# mcuBoard.net
KiCad netlist of a schematic drawn in EAGLE
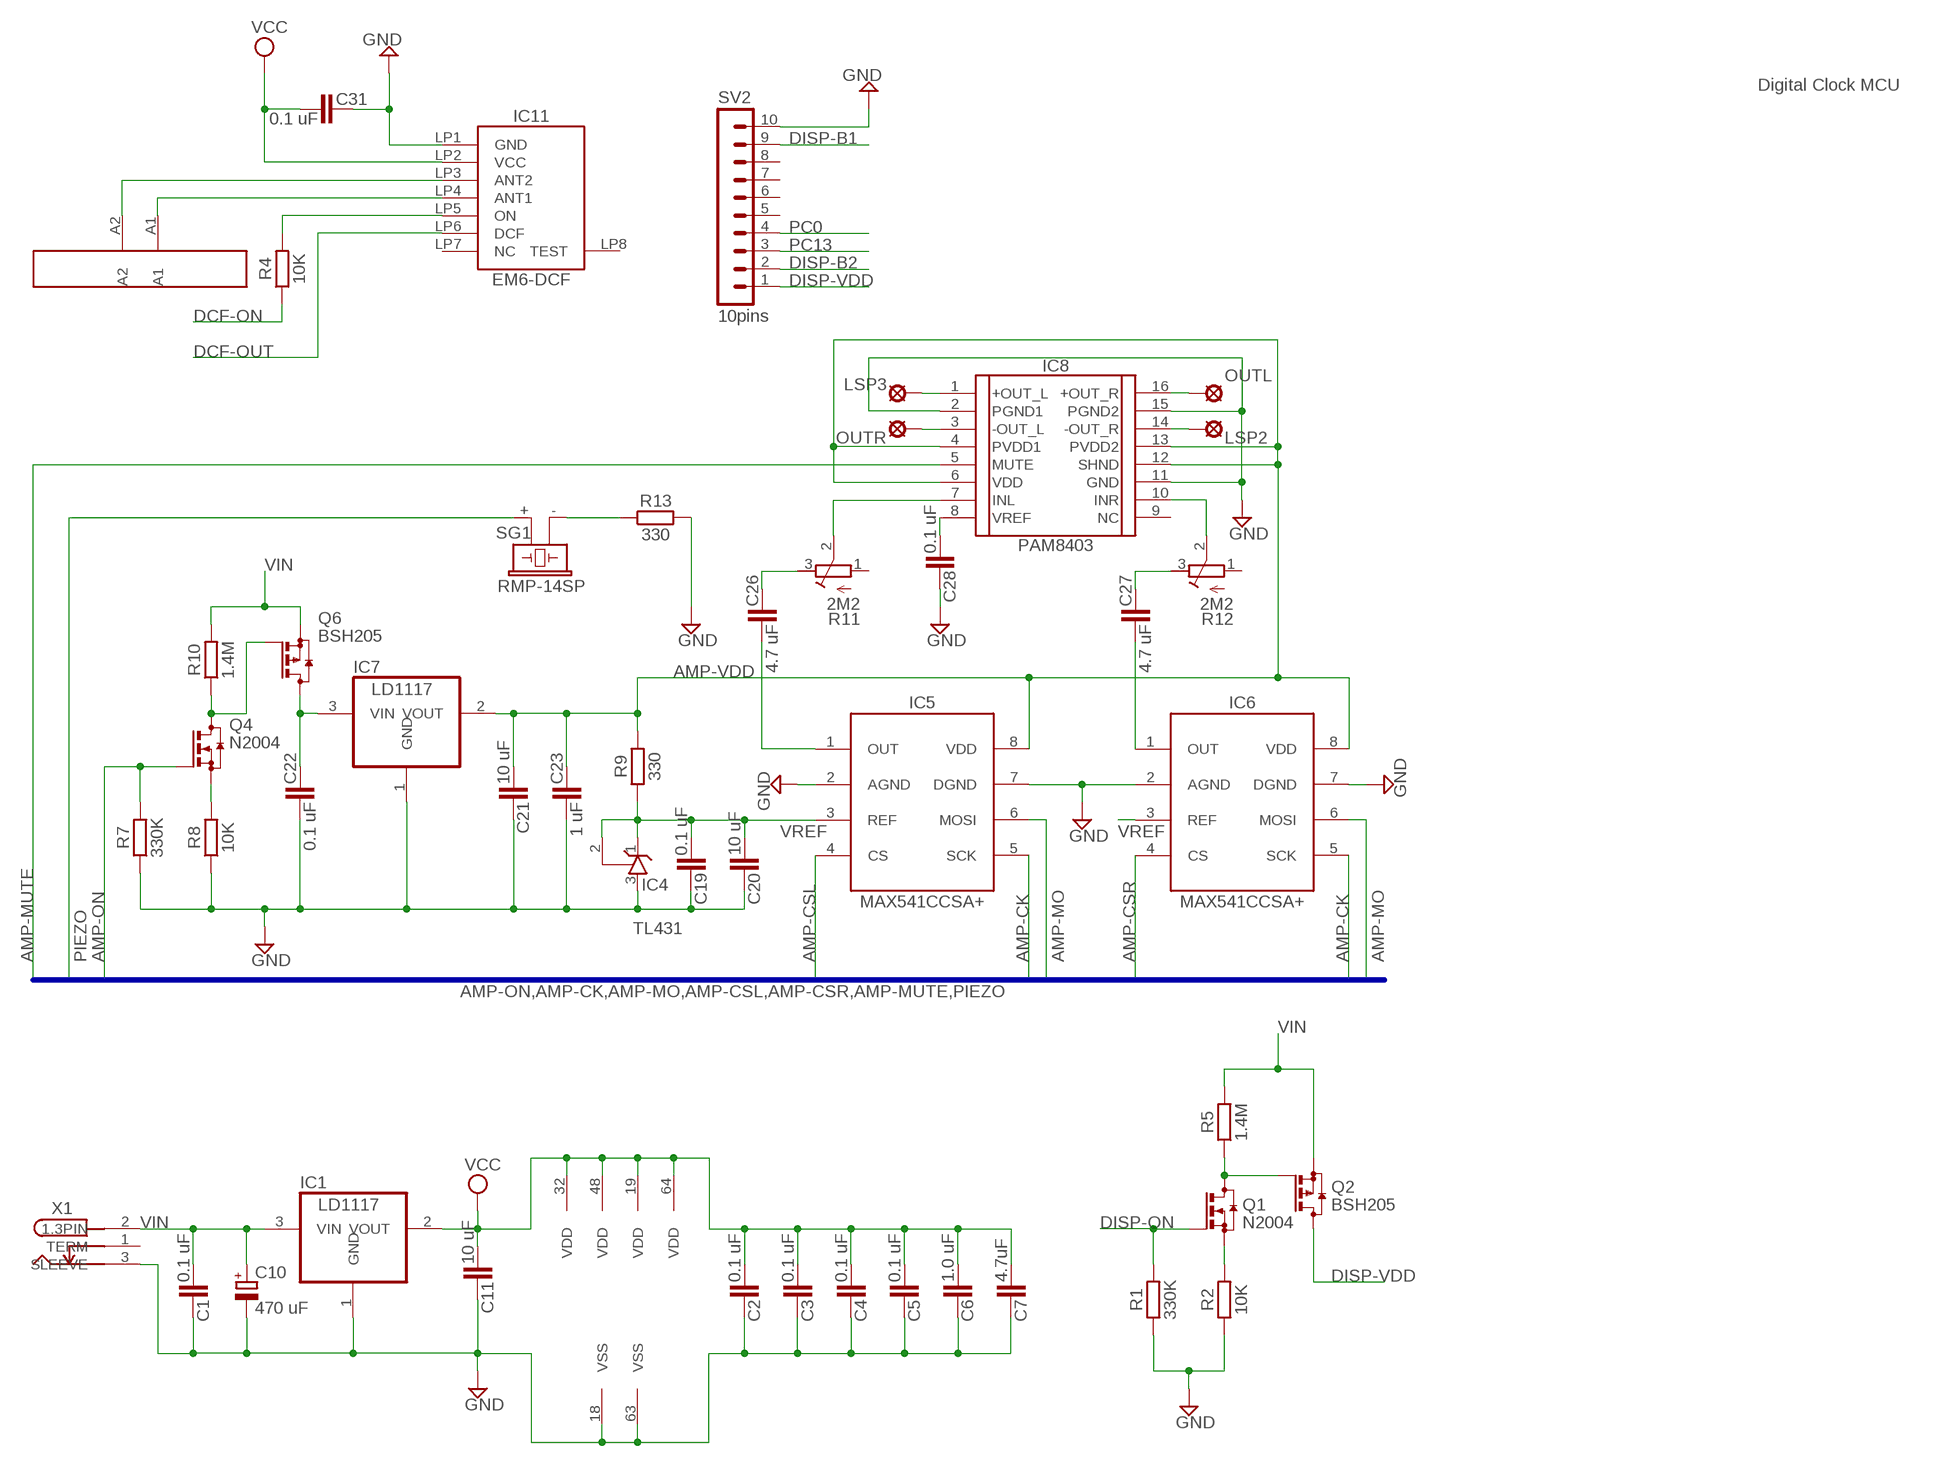
[diagram p0: schematic, sheet 1, part 1 of 2]
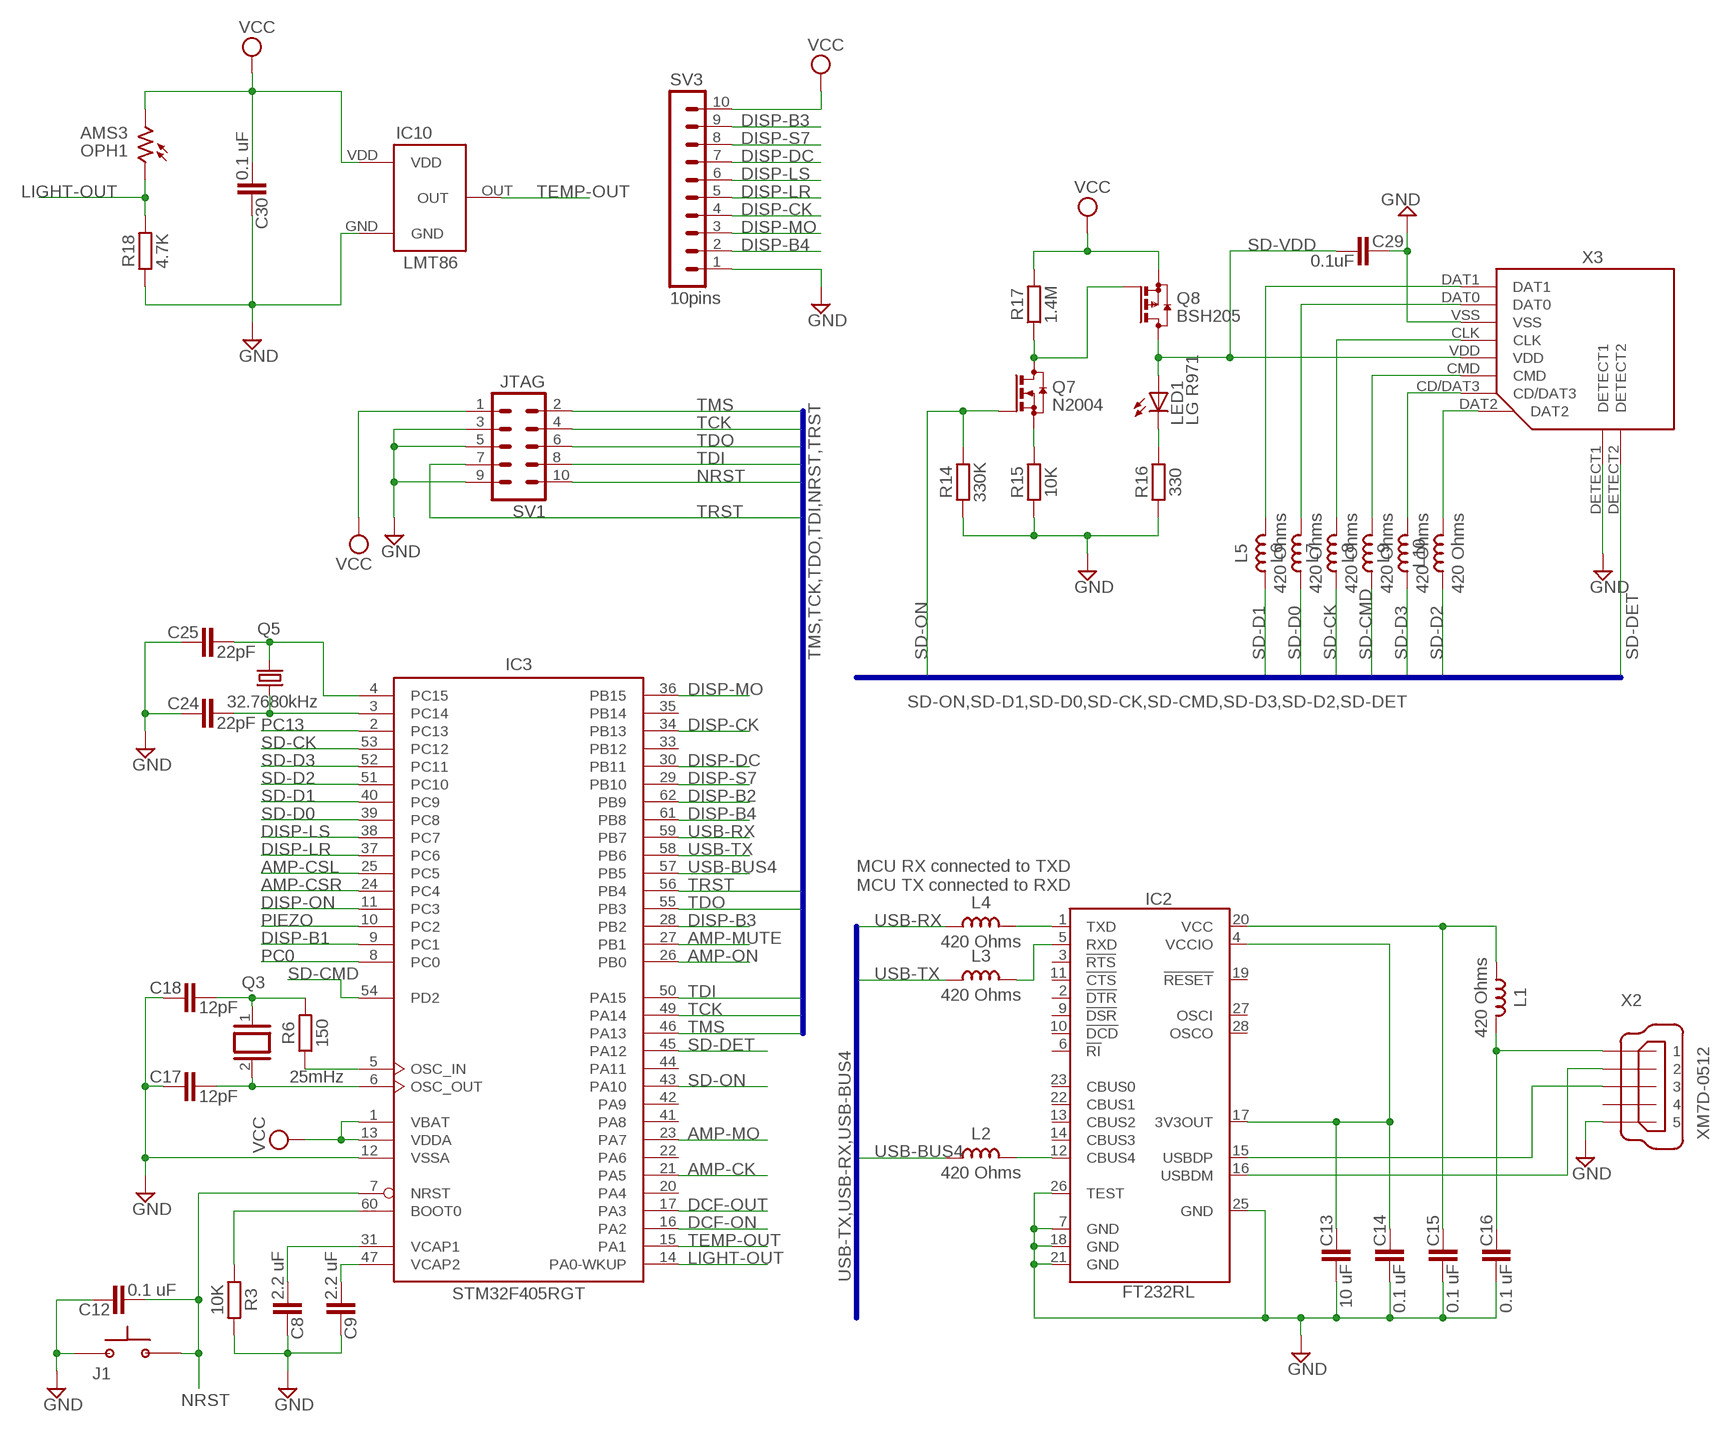
[diagram p1: schematic, sheet 1, part 2 of 2]

(export (version "E")
  (design (tool "Eeschema 10.0.6"))
  (components
    (comp (ref "A1")
      (value "DCF77-ANT")
      (footprint "eagle-import:DCF77-ANT")
      (libsource (lib "eagle-import") (part "DCF77-ANT"))
    )
    (comp (ref "C1")
      (value "0.1 uF")
      (footprint "eagle-import:C1206")
      (libsource (lib "eagle-import") (part "C-EUC1206"))
    )
    (comp (ref "C2")
      (value "0.1 uF")
      (footprint "eagle-import:C1206")
      (libsource (lib "eagle-import") (part "C-EUC1206"))
    )
    (comp (ref "C3")
      (value "0.1 uF")
      (footprint "eagle-import:C1206")
      (libsource (lib "eagle-import") (part "C-EUC1206"))
    )
    (comp (ref "C4")
      (value "0.1 uF")
      (footprint "eagle-import:C1206")
      (libsource (lib "eagle-import") (part "C-EUC1206"))
    )
    (comp (ref "C5")
      (value "0.1 uF")
      (footprint "eagle-import:C1206")
      (libsource (lib "eagle-import") (part "C-EUC1206"))
    )
    (comp (ref "C6")
      (value "1.0 uF")
      (footprint "eagle-import:C1206")
      (libsource (lib "eagle-import") (part "C-EUC1206"))
    )
    (comp (ref "C7")
      (value "4.7uF")
      (footprint "eagle-import:C1206")
      (libsource (lib "eagle-import") (part "C-EUC1206"))
    )
    (comp (ref "C8")
      (value "2.2 uF")
      (footprint "eagle-import:C1206")
      (libsource (lib "eagle-import") (part "C-EUC1206"))
    )
    (comp (ref "C9")
      (value "2.2 uF")
      (footprint "eagle-import:C1206")
      (libsource (lib "eagle-import") (part "C-EUC1206"))
    )
    (comp (ref "C10")
      (value "470 uF")
      (footprint "eagle-import:TT5D11L")
      (libsource (lib "eagle-import") (part "CPOL-EUTT5D11L"))
    )
    (comp (ref "C11")
      (value "10 uF")
      (footprint "eagle-import:C1206")
      (libsource (lib "eagle-import") (part "C-EUC1206"))
    )
    (comp (ref "C12")
      (value "0.1 uF")
      (footprint "eagle-import:C1206")
      (libsource (lib "eagle-import") (part "C-EUC1206"))
    )
    (comp (ref "C13")
      (value "10 uF")
      (footprint "eagle-import:C1206")
      (libsource (lib "eagle-import") (part "C-EUC1206"))
    )
    (comp (ref "C14")
      (value "0.1 uF")
      (footprint "eagle-import:C1206")
      (libsource (lib "eagle-import") (part "C-EUC1206"))
    )
    (comp (ref "C15")
      (value "0.1 uF")
      (footprint "eagle-import:C1206")
      (libsource (lib "eagle-import") (part "C-EUC1206"))
    )
    (comp (ref "C16")
      (value "0.1 uF")
      (footprint "eagle-import:C1206")
      (libsource (lib "eagle-import") (part "C-EUC1206"))
    )
    (comp (ref "C17")
      (value "12pF")
      (footprint "eagle-import:C1206")
      (libsource (lib "eagle-import") (part "C-EUC1206"))
    )
    (comp (ref "C18")
      (value "12pF")
      (footprint "eagle-import:C1206")
      (libsource (lib "eagle-import") (part "C-EUC1206"))
    )
    (comp (ref "C19")
      (value "0.1 uF")
      (footprint "eagle-import:C1206")
      (libsource (lib "eagle-import") (part "C-EUC1206"))
    )
    (comp (ref "C20")
      (value "10 uF")
      (footprint "eagle-import:C1206")
      (libsource (lib "eagle-import") (part "C-EUC1206"))
    )
    (comp (ref "C21")
      (value "10 uF")
      (footprint "eagle-import:C1206")
      (libsource (lib "eagle-import") (part "C-EUC1206"))
    )
    (comp (ref "C22")
      (value "0.1 uF")
      (footprint "eagle-import:C1206")
      (libsource (lib "eagle-import") (part "C-EUC1206"))
    )
    (comp (ref "C23")
      (value "1 uF")
      (footprint "eagle-import:C1206")
      (libsource (lib "eagle-import") (part "C-EUC1206"))
    )
    (comp (ref "C24")
      (value "22pF")
      (footprint "eagle-import:C1206")
      (libsource (lib "eagle-import") (part "C-EUC1206"))
    )
    (comp (ref "C25")
      (value "22pF")
      (footprint "eagle-import:C1206")
      (libsource (lib "eagle-import") (part "C-EUC1206"))
    )
    (comp (ref "C26")
      (value "4.7 uF")
      (footprint "eagle-import:C1206")
      (libsource (lib "eagle-import") (part "C-EUC1206"))
    )
    (comp (ref "C27")
      (value "4.7 uF")
      (footprint "eagle-import:C1206")
      (libsource (lib "eagle-import") (part "C-EUC1206"))
    )
    (comp (ref "C28")
      (value "0.1 uF")
      (footprint "eagle-import:C1206")
      (libsource (lib "eagle-import") (part "C-EUC1206"))
    )
    (comp (ref "C29")
      (value "0.1uF")
      (footprint "eagle-import:C1206")
      (libsource (lib "eagle-import") (part "C-EUC1206"))
    )
    (comp (ref "C30")
      (value "0.1 uF")
      (footprint "eagle-import:C1206")
      (libsource (lib "eagle-import") (part "C-EUC1206"))
    )
    (comp (ref "C31")
      (value "0.1 uF")
      (footprint "eagle-import:C1206")
      (libsource (lib "eagle-import") (part "C-EUC1206"))
    )
    (comp (ref "IC1")
      (value "LD1117")
      (footprint "eagle-import:SOT223")
      (fields (field (name "MPN") "REG1117"))
      (libsource (lib "eagle-import") (part "REG1117"))
    )
    (comp (ref "IC2")
      (value "FT232RL")
      (footprint "eagle-import:SSOP28")
      (libsource (lib "eagle-import") (part "FT232RL"))
    )
    (comp (ref "IC3")
      (value "STM32F405RGT")
      (footprint "eagle-import:LQFP64")
      (libsource (lib "eagle-import") (part "STM32F405RTG"))
    )
    (comp (ref "IC4")
      (value "TL431")
      (footprint "eagle-import:SOT-23")
      (libsource (lib "eagle-import") (part "TL431CL3T"))
    )
    (comp (ref "IC5")
      (value "MAX541CCSA+")
      (footprint "eagle-import:SOIC-8")
      (libsource (lib "eagle-import") (part "MAX541"))
    )
    (comp (ref "IC6")
      (value "MAX541CCSA+")
      (footprint "eagle-import:SOIC-8")
      (libsource (lib "eagle-import") (part "MAX541"))
    )
    (comp (ref "IC7")
      (value "LD1117")
      (footprint "eagle-import:SOT223")
      (fields (field (name "MPN") "REG1117"))
      (libsource (lib "eagle-import") (part "REG1117"))
    )
    (comp (ref "IC8")
      (value "PAM8403")
      (footprint "eagle-import:SOP-16")
      (libsource (lib "eagle-import") (part "PAM8403"))
    )
    (comp (ref "IC10")
      (value "LMT86")
      (footprint "eagle-import:LMT86")
      (libsource (lib "eagle-import") (part "LMT86"))
    )
    (comp (ref "IC11")
      (value "DCF77")
      (footprint "eagle-import:DCF77")
      (libsource (lib "eagle-import") (part "DCF77"))
    )
    (comp (ref "J1")
      (value "BUTTON-FSM14JRT")
      (footprint "eagle-import:BUTTON-FSM14JRT")
      (libsource (lib "eagle-import") (part "BUTTON-FSM14JRT"))
    )
    (comp (ref "L1")
      (value "420 Ohms")
      (footprint "eagle-import:L0603")
      (libsource (lib "eagle-import") (part "L0603"))
    )
    (comp (ref "L2")
      (value "420 Ohms")
      (footprint "eagle-import:L0603")
      (libsource (lib "eagle-import") (part "L0603"))
    )
    (comp (ref "L3")
      (value "420 Ohms")
      (footprint "eagle-import:L0603")
      (libsource (lib "eagle-import") (part "L0603"))
    )
    (comp (ref "L4")
      (value "420 Ohms")
      (footprint "eagle-import:L0603")
      (libsource (lib "eagle-import") (part "L0603"))
    )
    (comp (ref "L5")
      (value "420 Ohms")
      (footprint "eagle-import:L0603")
      (libsource (lib "eagle-import") (part "L0603"))
    )
    (comp (ref "L6")
      (value "420 Ohms")
      (footprint "eagle-import:L0603")
      (libsource (lib "eagle-import") (part "L0603"))
    )
    (comp (ref "L7")
      (value "420 Ohms")
      (footprint "eagle-import:L0603")
      (libsource (lib "eagle-import") (part "L0603"))
    )
    (comp (ref "L8")
      (value "420 Ohms")
      (footprint "eagle-import:L0603")
      (libsource (lib "eagle-import") (part "L0603"))
    )
    (comp (ref "L9")
      (value "420 Ohms")
      (footprint "eagle-import:L0603")
      (libsource (lib "eagle-import") (part "L0603"))
    )
    (comp (ref "L10")
      (value "420 Ohms")
      (footprint "eagle-import:L0603")
      (libsource (lib "eagle-import") (part "L0603"))
    )
    (comp (ref "LED1")
      (value "LG R971")
      (footprint "eagle-import:CHIP-LED0805")
      (libsource (lib "eagle-import") (part "LEDCHIP-LED0805"))
    )
    (comp (ref "LSP2")
      (value "LSP10")
      (footprint "eagle-import:LSP10")
      (libsource (lib "eagle-import") (part "LSP10"))
    )
    (comp (ref "LSP3")
      (value "LSP10")
      (footprint "eagle-import:LSP10")
      (libsource (lib "eagle-import") (part "LSP10"))
    )
    (comp (ref "OPH1")
      (value "AMS3")
      (footprint "eagle-import:VT900")
      (libsource (lib "eagle-import") (part "VT935GB"))
    )
    (comp (ref "OUTL")
      (value "LSP10")
      (footprint "eagle-import:LSP10")
      (libsource (lib "eagle-import") (part "LSP10"))
    )
    (comp (ref "OUTR")
      (value "LSP10")
      (footprint "eagle-import:LSP10")
      (libsource (lib "eagle-import") (part "LSP10"))
    )
    (comp (ref "Q1")
      (value "N2004")
      (footprint "eagle-import:SOT23")
      (libsource (lib "eagle-import") (part "BSS123"))
    )
    (comp (ref "Q2")
      (value "BSH205")
      (footprint "eagle-import:SOT23")
      (libsource (lib "eagle-import") (part "BSS84"))
    )
    (comp (ref "Q3")
      (value "25mHz")
      (footprint "eagle-import:HC-46X")
      (libsource (lib "eagle-import") (part "HC-46X"))
    )
    (comp (ref "Q4")
      (value "N2004")
      (footprint "eagle-import:SOT23")
      (libsource (lib "eagle-import") (part "BSS123"))
    )
    (comp (ref "Q5")
      (value "32.7680kHz")
      (footprint "eagle-import:MC-306")
      (fields (field (name "MPN") "MC-306 60.0KHZ  100PPM ,12.5PF"))
      (libsource (lib "eagle-import") (part "MC-306"))
    )
    (comp (ref "Q6")
      (value "BSH205")
      (footprint "eagle-import:SOT23")
      (libsource (lib "eagle-import") (part "BSS84"))
    )
    (comp (ref "Q7")
      (value "N2004")
      (footprint "eagle-import:SOT23")
      (libsource (lib "eagle-import") (part "BSS123"))
    )
    (comp (ref "Q8")
      (value "BSH205")
      (footprint "eagle-import:SOT23")
      (libsource (lib "eagle-import") (part "BSS84"))
    )
    (comp (ref "R1")
      (value "330K")
      (footprint "eagle-import:R1206")
      (libsource (lib "eagle-import") (part "R-EU_R1206"))
    )
    (comp (ref "R2")
      (value "10K")
      (footprint "eagle-import:R1206")
      (libsource (lib "eagle-import") (part "R-EU_R1206"))
    )
    (comp (ref "R3")
      (value "10K")
      (footprint "eagle-import:R1206")
      (libsource (lib "eagle-import") (part "R-EU_R1206"))
    )
    (comp (ref "R4")
      (value "10K")
      (footprint "eagle-import:R1206")
      (libsource (lib "eagle-import") (part "R-EU_R1206"))
    )
    (comp (ref "R5")
      (value "1.4M")
      (footprint "eagle-import:R1206")
      (libsource (lib "eagle-import") (part "R-EU_R1206"))
    )
    (comp (ref "R6")
      (value "150")
      (footprint "eagle-import:R1206")
      (libsource (lib "eagle-import") (part "R-EU_R1206"))
    )
    (comp (ref "R7")
      (value "330K")
      (footprint "eagle-import:R1206")
      (libsource (lib "eagle-import") (part "R-EU_R1206"))
    )
    (comp (ref "R8")
      (value "10K")
      (footprint "eagle-import:R1206")
      (libsource (lib "eagle-import") (part "R-EU_R1206"))
    )
    (comp (ref "R9")
      (value "330")
      (footprint "eagle-import:R1206")
      (libsource (lib "eagle-import") (part "R-EU_R1206"))
    )
    (comp (ref "R10")
      (value "1.4M")
      (footprint "eagle-import:R1206")
      (libsource (lib "eagle-import") (part "R-EU_R1206"))
    )
    (comp (ref "R11")
      (value "2M2")
      (footprint "eagle-import:R-TRIM-3362U")
      (libsource (lib "eagle-import") (part "R-TRIM3362U"))
    )
    (comp (ref "R12")
      (value "2M2")
      (footprint "eagle-import:R-TRIM-3362U")
      (libsource (lib "eagle-import") (part "R-TRIM3362U"))
    )
    (comp (ref "R13")
      (value "330")
      (footprint "eagle-import:R1206")
      (libsource (lib "eagle-import") (part "R-EU_R1206"))
    )
    (comp (ref "R14")
      (value "330K")
      (footprint "eagle-import:R1206")
      (libsource (lib "eagle-import") (part "R-EU_R1206"))
    )
    (comp (ref "R15")
      (value "10K")
      (footprint "eagle-import:R1206")
      (libsource (lib "eagle-import") (part "R-EU_R1206"))
    )
    (comp (ref "R16")
      (value "330")
      (footprint "eagle-import:R1206")
      (libsource (lib "eagle-import") (part "R-EU_R1206"))
    )
    (comp (ref "R17")
      (value "1.4M")
      (footprint "eagle-import:R1206")
      (libsource (lib "eagle-import") (part "R-EU_R1206"))
    )
    (comp (ref "R18")
      (value "4.7K")
      (footprint "eagle-import:R1206")
      (libsource (lib "eagle-import") (part "R-EU_R1206"))
    )
    (comp (ref "SG1")
      (value "RMP-14SP")
      (footprint "eagle-import:F_CM12P")
      (libsource (lib "eagle-import") (part "F/CM12P"))
    )
    (comp (ref "SV1")
      (value "JTAG")
      (footprint "eagle-import:MA05-2")
      (libsource (lib "eagle-import") (part "MA05-2"))
    )
    (comp (ref "SV2")
      (value "10pins")
      (footprint "eagle-import:MA10-1")
      (libsource (lib "eagle-import") (part "MA10-1"))
    )
    (comp (ref "SV3")
      (value "10pins")
      (footprint "eagle-import:MA10-1")
      (libsource (lib "eagle-import") (part "MA10-1"))
    )
    (comp (ref "X1")
      (value "DC-8N")
      (footprint "eagle-import:BUCHSE-1.3X3.75")
      (libsource (lib "eagle-import") (part "DC-8N"))
    )
    (comp (ref "X2")
      (value "XM7D-0512")
      (footprint "eagle-import:XM7D-0512")
      (libsource (lib "eagle-import") (part "MINI-USB-5-DPI32005-601"))
    )
    (comp (ref "X3")
      (value "MICRO-SD-DM3AT")
      (footprint "eagle-import:DM3AT")
      (libsource (lib "eagle-import") (part "MICRO-SD-DM3AT"))
    )
  )
  (nets
    (net (code "1") (name "/AMP-CK") (class "Default")
      (node (ref "IC3") (pin "21") (pinfunction "PA5_21") (pintype "bidirectional"))
      (node (ref "IC5") (pin "5") (pinfunction "SCK_5") (pintype "bidirectional"))
      (node (ref "IC6") (pin "5") (pinfunction "SCK_5") (pintype "bidirectional"))
    )
    (net (code "2") (name "/AMP-CSL") (class "Default")
      (node (ref "IC3") (pin "25") (pinfunction "PC5_25") (pintype "bidirectional"))
      (node (ref "IC5") (pin "4") (pinfunction "CS_4") (pintype "bidirectional"))
    )
    (net (code "3") (name "/AMP-CSR") (class "Default")
      (node (ref "IC3") (pin "24") (pinfunction "PC4_24") (pintype "bidirectional"))
      (node (ref "IC6") (pin "4") (pinfunction "CS_4") (pintype "bidirectional"))
    )
    (net (code "4") (name "/AMP-MO") (class "Default")
      (node (ref "IC3") (pin "23") (pinfunction "PA7_23") (pintype "bidirectional"))
      (node (ref "IC5") (pin "6") (pinfunction "MOSI_6") (pintype "bidirectional"))
      (node (ref "IC6") (pin "6") (pinfunction "MOSI_6") (pintype "bidirectional"))
    )
    (net (code "5") (name "/AMP-MUTE") (class "Default")
      (node (ref "IC3") (pin "27") (pinfunction "PB1_27") (pintype "bidirectional"))
      (node (ref "IC8") (pin "5") (pinfunction "MUTE_5") (pintype "bidirectional"))
    )
    (net (code "6") (name "/AMP-ON") (class "Default")
      (node (ref "IC3") (pin "26") (pinfunction "PB0_26") (pintype "bidirectional"))
      (node (ref "Q4") (pin "1") (pinfunction "G_1") (pintype "passive"))
      (node (ref "R7") (pin "2") (pinfunction "2_2") (pintype "passive"))
    )
    (net (code "7") (name "/AMP-VDD") (class "Default")
      (node (ref "C21") (pin "2") (pinfunction "2_2") (pintype "passive"))
      (node (ref "C23") (pin "1") (pinfunction "1_1") (pintype "passive"))
      (node (ref "IC5") (pin "8") (pinfunction "VDD_8") (pintype "bidirectional"))
      (node (ref "IC6") (pin "8") (pinfunction "VDD_8") (pintype "bidirectional"))
      (node (ref "IC7") (pin "2") (pinfunction "VOUT_2") (pintype "power_in"))
      (node (ref "IC8") (pin "12") (pinfunction "SHND_12") (pintype "bidirectional"))
      (node (ref "IC8") (pin "13") (pinfunction "PVDD2_13") (pintype "bidirectional"))
      (node (ref "IC8") (pin "4") (pinfunction "PVDD1_4") (pintype "bidirectional"))
      (node (ref "IC8") (pin "6") (pinfunction "VDD_6") (pintype "bidirectional"))
      (node (ref "R9") (pin "2") (pinfunction "2_2") (pintype "passive"))
    )
    (net (code "8") (name "/DCF-ON") (class "Default")
      (node (ref "IC3") (pin "16") (pinfunction "PA2_16") (pintype "bidirectional"))
      (node (ref "R4") (pin "1") (pinfunction "1_1") (pintype "passive"))
    )
    (net (code "9") (name "/DCF-OUT") (class "Default")
      (node (ref "IC11") (pin "LP6") (pinfunction "DCF_LP6") (pintype "bidirectional"))
      (node (ref "IC3") (pin "17") (pinfunction "PA3_17") (pintype "bidirectional"))
    )
    (net (code "10") (name "/DISP-B1") (class "Default")
      (node (ref "IC3") (pin "9") (pinfunction "PC1_9") (pintype "bidirectional"))
      (node (ref "SV2") (pin "9") (pinfunction "9_9") (pintype "passive"))
    )
    (net (code "11") (name "/DISP-B2") (class "Default")
      (node (ref "IC3") (pin "62") (pinfunction "PB9_62") (pintype "bidirectional"))
      (node (ref "SV2") (pin "2") (pinfunction "2_2") (pintype "passive"))
    )
    (net (code "12") (name "/DISP-B3") (class "Default")
      (node (ref "IC3") (pin "28") (pinfunction "PB2_28") (pintype "bidirectional"))
      (node (ref "SV3") (pin "9") (pinfunction "9_9") (pintype "passive"))
    )
    (net (code "13") (name "/DISP-B4") (class "Default")
      (node (ref "IC3") (pin "61") (pinfunction "PB8_61") (pintype "bidirectional"))
      (node (ref "SV3") (pin "2") (pinfunction "2_2") (pintype "passive"))
    )
    (net (code "14") (name "/DISP-CK") (class "Default")
      (node (ref "IC3") (pin "34") (pinfunction "PB13_34") (pintype "bidirectional"))
      (node (ref "SV3") (pin "4") (pinfunction "4_4") (pintype "passive"))
    )
    (net (code "15") (name "/DISP-DC") (class "Default")
      (node (ref "IC3") (pin "30") (pinfunction "PB11_30") (pintype "bidirectional"))
      (node (ref "SV3") (pin "7") (pinfunction "7_7") (pintype "passive"))
    )
    (net (code "16") (name "/DISP-LR") (class "Default")
      (node (ref "IC3") (pin "37") (pinfunction "PC6_37") (pintype "bidirectional"))
      (node (ref "SV3") (pin "5") (pinfunction "5_5") (pintype "passive"))
    )
    (net (code "17") (name "/DISP-LS") (class "Default")
      (node (ref "IC3") (pin "38") (pinfunction "PC7_38") (pintype "bidirectional"))
      (node (ref "SV3") (pin "6") (pinfunction "6_6") (pintype "passive"))
    )
    (net (code "18") (name "/DISP-MO") (class "Default")
      (node (ref "IC3") (pin "36") (pinfunction "PB15_36") (pintype "bidirectional"))
      (node (ref "SV3") (pin "3") (pinfunction "3_3") (pintype "passive"))
    )
    (net (code "19") (name "/DISP-ON") (class "Default")
      (node (ref "IC3") (pin "11") (pinfunction "PC3_11") (pintype "bidirectional"))
      (node (ref "Q1") (pin "1") (pinfunction "G_1") (pintype "passive"))
      (node (ref "R1") (pin "2") (pinfunction "2_2") (pintype "passive"))
    )
    (net (code "20") (name "/DISP-S7") (class "Default")
      (node (ref "IC3") (pin "29") (pinfunction "PB10_29") (pintype "bidirectional"))
      (node (ref "SV3") (pin "8") (pinfunction "8_8") (pintype "passive"))
    )
    (net (code "21") (name "/DISP-VDD") (class "Default")
      (node (ref "Q2") (pin "3") (pinfunction "D_3") (pintype "passive"))
      (node (ref "SV2") (pin "1") (pinfunction "1_1") (pintype "passive"))
    )
    (net (code "22") (name "/LIGHT-OUT") (class "Default")
      (node (ref "IC3") (pin "14") (pinfunction "PA0-WKUP_14") (pintype "bidirectional"))
      (node (ref "OPH1") (pin "1") (pinfunction "1_1") (pintype "passive"))
      (node (ref "R18") (pin "2") (pinfunction "2_2") (pintype "passive"))
    )
    (net (code "23") (name "/NRST") (class "Default")
      (node (ref "C12") (pin "2") (pinfunction "2_2") (pintype "passive"))
      (node (ref "IC3") (pin "7") (pinfunction "NRST_7") (pintype "bidirectional"))
      (node (ref "J1") (pin "P$2") (pinfunction "2_P$2") (pintype "bidirectional"))
      (node (ref "SV1") (pin "10") (pinfunction "10_10") (pintype "passive"))
    )
    (net (code "24") (name "/PC0") (class "Default")
      (node (ref "IC3") (pin "8") (pinfunction "PC0_8") (pintype "bidirectional"))
      (node (ref "SV2") (pin "4") (pinfunction "4_4") (pintype "passive"))
    )
    (net (code "25") (name "/PC13") (class "Default")
      (node (ref "IC3") (pin "2") (pinfunction "PC13_2") (pintype "bidirectional"))
      (node (ref "SV2") (pin "3") (pinfunction "3_3") (pintype "passive"))
    )
    (net (code "26") (name "/PIEZO") (class "Default")
      (node (ref "IC3") (pin "10") (pinfunction "PC2_10") (pintype "bidirectional"))
      (node (ref "SG1") (pin "+") (pinfunction "1_+") (pintype "passive"))
    )
    (net (code "27") (name "/SD-CK") (class "Default")
      (node (ref "IC3") (pin "53") (pinfunction "PC12_53") (pintype "bidirectional"))
      (node (ref "L7") (pin "1") (pinfunction "1_1") (pintype "passive"))
    )
    (net (code "28") (name "/SD-CMD") (class "Default")
      (node (ref "IC3") (pin "54") (pinfunction "PD2_54") (pintype "bidirectional"))
      (node (ref "L8") (pin "1") (pinfunction "1_1") (pintype "passive"))
    )
    (net (code "29") (name "/SD-D0") (class "Default")
      (node (ref "IC3") (pin "39") (pinfunction "PC8_39") (pintype "bidirectional"))
      (node (ref "L6") (pin "1") (pinfunction "1_1") (pintype "passive"))
    )
    (net (code "30") (name "/SD-D1") (class "Default")
      (node (ref "IC3") (pin "40") (pinfunction "PC9_40") (pintype "bidirectional"))
      (node (ref "L5") (pin "1") (pinfunction "1_1") (pintype "passive"))
    )
    (net (code "31") (name "/SD-D2") (class "Default")
      (node (ref "IC3") (pin "51") (pinfunction "PC10_51") (pintype "bidirectional"))
      (node (ref "L10") (pin "1") (pinfunction "1_1") (pintype "passive"))
    )
    (net (code "32") (name "/SD-D3") (class "Default")
      (node (ref "IC3") (pin "52") (pinfunction "PC11_52") (pintype "bidirectional"))
      (node (ref "L9") (pin "1") (pinfunction "1_1") (pintype "passive"))
    )
    (net (code "33") (name "/SD-DET") (class "Default")
      (node (ref "IC3") (pin "45") (pinfunction "PA12_45") (pintype "bidirectional"))
      (node (ref "X3") (pin "DETECT2") (pinfunction "DETECT2_DETECT2") (pintype "bidirectional"))
    )
    (net (code "34") (name "/SD-ON") (class "Default")
      (node (ref "IC3") (pin "43") (pinfunction "PA10_43") (pintype "bidirectional"))
      (node (ref "Q7") (pin "1") (pinfunction "G_1") (pintype "passive"))
      (node (ref "R14") (pin "2") (pinfunction "2_2") (pintype "passive"))
    )
    (net (code "35") (name "/SD-VDD") (class "Default")
      (node (ref "C29") (pin "2") (pinfunction "2_2") (pintype "passive"))
      (node (ref "LED1") (pin "A") (pinfunction "A_A") (pintype "passive"))
      (node (ref "Q8") (pin "3") (pinfunction "D_3") (pintype "passive"))
      (node (ref "X3") (pin "VDD") (pinfunction "VDD_VDD") (pintype "power_in"))
    )
    (net (code "36") (name "/TCK") (class "Default")
      (node (ref "IC3") (pin "49") (pinfunction "PA14_49") (pintype "bidirectional"))
      (node (ref "SV1") (pin "4") (pinfunction "4_4") (pintype "passive"))
    )
    (net (code "37") (name "/TDI") (class "Default")
      (node (ref "IC3") (pin "50") (pinfunction "PA15_50") (pintype "bidirectional"))
      (node (ref "SV1") (pin "8") (pinfunction "8_8") (pintype "passive"))
    )
    (net (code "38") (name "/TDO") (class "Default")
      (node (ref "IC3") (pin "55") (pinfunction "PB3_55") (pintype "bidirectional"))
      (node (ref "SV1") (pin "6") (pinfunction "6_6") (pintype "passive"))
    )
    (net (code "39") (name "/TEMP-OUT") (class "Default")
      (node (ref "IC10") (pin "OUT") (pinfunction "OUT_OUT") (pintype "bidirectional"))
      (node (ref "IC3") (pin "15") (pinfunction "PA1_15") (pintype "bidirectional"))
    )
    (net (code "40") (name "/TMS") (class "Default")
      (node (ref "IC3") (pin "46") (pinfunction "PA13_46") (pintype "bidirectional"))
      (node (ref "SV1") (pin "2") (pinfunction "2_2") (pintype "passive"))
    )
    (net (code "41") (name "/TRST") (class "Default")
      (node (ref "IC3") (pin "56") (pinfunction "PB4_56") (pintype "bidirectional"))
      (node (ref "SV1") (pin "7") (pinfunction "7_7") (pintype "passive"))
    )
    (net (code "42") (name "/USB-BUS4") (class "Default")
      (node (ref "IC3") (pin "57") (pinfunction "PB5_57") (pintype "bidirectional"))
      (node (ref "L2") (pin "2") (pinfunction "2_2") (pintype "passive"))
    )
    (net (code "43") (name "/USB-RX") (class "Default")
      (node (ref "IC3") (pin "59") (pinfunction "PB7_59") (pintype "bidirectional"))
      (node (ref "L4") (pin "1") (pinfunction "1_1") (pintype "passive"))
    )
    (net (code "44") (name "/USB-TX") (class "Default")
      (node (ref "IC3") (pin "58") (pinfunction "PB6_58") (pintype "bidirectional"))
      (node (ref "L3") (pin "1") (pinfunction "1_1") (pintype "passive"))
    )
    (net (code "45") (name "/VIN") (class "Default")
      (node (ref "C1") (pin "2") (pinfunction "2_2") (pintype "passive"))
      (node (ref "C10") (pin "+") (pinfunction "+_+") (pintype "passive"))
      (node (ref "IC1") (pin "3") (pinfunction "VIN_3") (pintype "input"))
      (node (ref "Q2") (pin "2") (pinfunction "S_2") (pintype "passive"))
      (node (ref "Q6") (pin "2") (pinfunction "S_2") (pintype "passive"))
      (node (ref "R10") (pin "2") (pinfunction "2_2") (pintype "passive"))
      (node (ref "R5") (pin "2") (pinfunction "2_2") (pintype "passive"))
      (node (ref "X1") (pin "2") (pinfunction "1.3PIN_2") (pintype "power_in"))
    )
    (net (code "46") (name "/VREF") (class "Default")
      (node (ref "C19") (pin "2") (pinfunction "2_2") (pintype "passive"))
      (node (ref "C20") (pin "2") (pinfunction "2_2") (pintype "passive"))
      (node (ref "IC4") (pin "1") (pinfunction "C_1") (pintype "passive"))
      (node (ref "IC4") (pin "2") (pinfunction "R_2") (pintype "passive"))
      (node (ref "IC5") (pin "3") (pinfunction "REF_3") (pintype "bidirectional"))
      (node (ref "IC6") (pin "3") (pinfunction "REF_3") (pintype "bidirectional"))
      (node (ref "R9") (pin "1") (pinfunction "1_1") (pintype "passive"))
    )
    (net (code "51") (name "GND") (class "Default")
      (node (ref "C1") (pin "1") (pinfunction "1_1") (pintype "passive"))
      (node (ref "C10") (pin "-") (pinfunction "-_-") (pintype "passive"))
      (node (ref "C11") (pin "1") (pinfunction "1_1") (pintype "passive"))
      (node (ref "C12") (pin "1") (pinfunction "1_1") (pintype "passive"))
      (node (ref "C13") (pin "2") (pinfunction "2_2") (pintype "passive"))
      (node (ref "C14") (pin "2") (pinfunction "2_2") (pintype "passive"))
      (node (ref "C15") (pin "2") (pinfunction "2_2") (pintype "passive"))
      (node (ref "C16") (pin "2") (pinfunction "2_2") (pintype "passive"))
      (node (ref "C17") (pin "1") (pinfunction "1_1") (pintype "passive"))
      (node (ref "C18") (pin "1") (pinfunction "1_1") (pintype "passive"))
      (node (ref "C19") (pin "1") (pinfunction "1_1") (pintype "passive"))
      (node (ref "C2") (pin "1") (pinfunction "1_1") (pintype "passive"))
      (node (ref "C20") (pin "1") (pinfunction "1_1") (pintype "passive"))
      (node (ref "C21") (pin "1") (pinfunction "1_1") (pintype "passive"))
      (node (ref "C22") (pin "2") (pinfunction "2_2") (pintype "passive"))
      (node (ref "C23") (pin "2") (pinfunction "2_2") (pintype "passive"))
      (node (ref "C24") (pin "1") (pinfunction "1_1") (pintype "passive"))
      (node (ref "C25") (pin "1") (pinfunction "1_1") (pintype "passive"))
      (node (ref "C28") (pin "1") (pinfunction "1_1") (pintype "passive"))
      (node (ref "C29") (pin "1") (pinfunction "1_1") (pintype "passive"))
      (node (ref "C3") (pin "1") (pinfunction "1_1") (pintype "passive"))
      (node (ref "C30") (pin "1") (pinfunction "1_1") (pintype "passive"))
      (node (ref "C31") (pin "1") (pinfunction "1_1") (pintype "passive"))
      (node (ref "C4") (pin "1") (pinfunction "1_1") (pintype "passive"))
      (node (ref "C5") (pin "1") (pinfunction "1_1") (pintype "passive"))
      (node (ref "C6") (pin "1") (pinfunction "1_1") (pintype "passive"))
      (node (ref "C7") (pin "1") (pinfunction "1_1") (pintype "passive"))
      (node (ref "C8") (pin "1") (pinfunction "1_1") (pintype "passive"))
      (node (ref "C9") (pin "1") (pinfunction "1_1") (pintype "passive"))
      (node (ref "IC1") (pin "1") (pinfunction "GND_1") (pintype "power_in"))
      (node (ref "IC10") (pin "GND") (pinfunction "GND_GND") (pintype "power_in"))
      (node (ref "IC11") (pin "LP1") (pinfunction "GND_LP1") (pintype "power_in"))
      (node (ref "IC2") (pin "18") (pinfunction "GND_18") (pintype "power_in"))
      (node (ref "IC2") (pin "21") (pinfunction "GND_21") (pintype "power_in"))
      (node (ref "IC2") (pin "25") (pinfunction "GND_25") (pintype "power_in"))
      (node (ref "IC2") (pin "26") (pinfunction "TEST_26") (pintype "input"))
      (node (ref "IC2") (pin "7") (pinfunction "GND_7") (pintype "power_in"))
      (node (ref "IC3") (pin "12") (pinfunction "VSSA_12") (pintype "power_in"))
      (node (ref "IC3") (pin "18") (pinfunction "VSS_18") (pintype "power_in"))
      (node (ref "IC3") (pin "63") (pinfunction "VSS_63") (pintype "power_in"))
      (node (ref "IC4") (pin "3") (pinfunction "A_3") (pintype "passive"))
      (node (ref "IC5") (pin "2") (pinfunction "AGND_2") (pintype "bidirectional"))
      (node (ref "IC5") (pin "7") (pinfunction "DGND_7") (pintype "bidirectional"))
      (node (ref "IC6") (pin "2") (pinfunction "AGND_2") (pintype "bidirectional"))
      (node (ref "IC6") (pin "7") (pinfunction "DGND_7") (pintype "bidirectional"))
      (node (ref "IC7") (pin "1") (pinfunction "GND_1") (pintype "power_in"))
      (node (ref "IC8") (pin "11") (pinfunction "GND_11") (pintype "bidirectional"))
      (node (ref "IC8") (pin "15") (pinfunction "PGND2_15") (pintype "bidirectional"))
      (node (ref "IC8") (pin "2") (pinfunction "PGND1_2") (pintype "bidirectional"))
      (node (ref "J1") (pin "P$1") (pinfunction "1_P$1") (pintype "bidirectional"))
      (node (ref "R1") (pin "1") (pinfunction "1_1") (pintype "passive"))
      (node (ref "R13") (pin "2") (pinfunction "2_2") (pintype "passive"))
      (node (ref "R14") (pin "1") (pinfunction "1_1") (pintype "passive"))
      (node (ref "R15") (pin "1") (pinfunction "1_1") (pintype "passive"))
      (node (ref "R16") (pin "1") (pinfunction "1_1") (pintype "passive"))
      (node (ref "R18") (pin "1") (pinfunction "1_1") (pintype "passive"))
      (node (ref "R2") (pin "1") (pinfunction "1_1") (pintype "passive"))
      (node (ref "R3") (pin "2") (pinfunction "2_2") (pintype "passive"))
      (node (ref "R7") (pin "1") (pinfunction "1_1") (pintype "passive"))
      (node (ref "R8") (pin "1") (pinfunction "1_1") (pintype "passive"))
      (node (ref "SV1") (pin "3") (pinfunction "3_3") (pintype "passive"))
      (node (ref "SV1") (pin "5") (pinfunction "5_5") (pintype "passive"))
      (node (ref "SV1") (pin "9") (pinfunction "9_9") (pintype "passive"))
      (node (ref "SV2") (pin "10") (pinfunction "10_10") (pintype "passive"))
      (node (ref "SV3") (pin "1") (pinfunction "1_1") (pintype "passive"))
      (node (ref "X1") (pin "3") (pinfunction "SLEEVE_3") (pintype "power_in"))
      (node (ref "X2") (pin "5") (pinfunction "5_5") (pintype "passive"))
      (node (ref "X3") (pin "DETECT1") (pinfunction "DETECT1_DETECT1") (pintype "bidirectional"))
      (node (ref "X3") (pin "VSS") (pinfunction "VSS_VSS") (pintype "power_in"))
    )
    (net (code "52") (name "Net-(C16-Pad1)") (class "Default")
      (node (ref "C16") (pin "1") (pinfunction "1_1") (pintype "passive"))
      (node (ref "L1") (pin "2") (pinfunction "2_2") (pintype "passive"))
      (node (ref "X2") (pin "1") (pinfunction "1_1") (pintype "passive"))
    )
    (net (code "53") (name "Net-(C18-Pad2)") (class "Default")
      (node (ref "C18") (pin "2") (pinfunction "2_2") (pintype "passive"))
      (node (ref "Q3") (pin "1") (pinfunction "1_1") (pintype "passive"))
      (node (ref "R6") (pin "2") (pinfunction "2_2") (pintype "passive"))
    )
    (net (code "54") (name "Net-(C26-Pad1)") (class "Default")
      (node (ref "C26") (pin "1") (pinfunction "1_1") (pintype "passive"))
      (node (ref "R11") (pin "3") (pinfunction "3_3") (pintype "passive"))
    )
    (net (code "55") (name "Net-(C27-Pad1)") (class "Default")
      (node (ref "C27") (pin "1") (pinfunction "1_1") (pintype "passive"))
      (node (ref "R12") (pin "3") (pinfunction "3_3") (pintype "passive"))
    )
    (net (code "56") (name "Net-(IC2-3V3OUT)") (class "Default")
      (node (ref "C13") (pin "1") (pinfunction "1_1") (pintype "passive"))
      (node (ref "C14") (pin "1") (pinfunction "1_1") (pintype "passive"))
      (node (ref "IC2") (pin "17") (pinfunction "3V3OUT_17") (pintype "output"))
      (node (ref "IC2") (pin "4") (pinfunction "VCCIO_4") (pintype "power_in"))
    )
    (net (code "57") (name "Net-(IC2-CBUS4)") (class "Default")
      (node (ref "IC2") (pin "12") (pinfunction "CBUS4_12") (pintype "bidirectional"))
      (node (ref "L2") (pin "1") (pinfunction "1_1") (pintype "passive"))
    )
    (net (code "58") (name "Net-(IC2-RXD)") (class "Default")
      (node (ref "IC2") (pin "5") (pinfunction "RXD_5") (pintype "input"))
      (node (ref "L3") (pin "2") (pinfunction "2_2") (pintype "passive"))
    )
    (net (code "59") (name "Net-(IC2-TXD)") (class "Default")
      (node (ref "IC2") (pin "1") (pinfunction "TXD_1") (pintype "output"))
      (node (ref "L4") (pin "2") (pinfunction "2_2") (pintype "passive"))
    )
    (net (code "60") (name "Net-(IC2-USBDM)") (class "Default")
      (node (ref "IC2") (pin "16") (pinfunction "USBDM_16") (pintype "bidirectional"))
      (node (ref "X2") (pin "2") (pinfunction "2_2") (pintype "passive"))
    )
    (net (code "61") (name "Net-(IC2-USBDP)") (class "Default")
      (node (ref "IC2") (pin "15") (pinfunction "USBDP_15") (pintype "bidirectional"))
      (node (ref "X2") (pin "3") (pinfunction "3_3") (pintype "passive"))
    )
    (net (code "62") (name "Net-(IC2-VCC)") (class "Default")
      (node (ref "C15") (pin "1") (pinfunction "1_1") (pintype "passive"))
      (node (ref "IC2") (pin "20") (pinfunction "VCC_20") (pintype "power_in"))
      (node (ref "L1") (pin "1") (pinfunction "1_1") (pintype "passive"))
    )
    (net (code "63") (name "Net-(IC3A-BOOT0)") (class "Default")
      (node (ref "IC3") (pin "60") (pinfunction "BOOT0_60") (pintype "input"))
      (node (ref "R3") (pin "1") (pinfunction "1_1") (pintype "passive"))
    )
    (net (code "64") (name "Net-(IC3A-OSC_IN)") (class "Default")
      (node (ref "IC3") (pin "5") (pinfunction "OSC_IN_5") (pintype "bidirectional"))
      (node (ref "R6") (pin "1") (pinfunction "1_1") (pintype "passive"))
    )
    (net (code "65") (name "Net-(IC3A-OSC_OUT)") (class "Default")
      (node (ref "C17") (pin "2") (pinfunction "2_2") (pintype "passive"))
      (node (ref "IC3") (pin "6") (pinfunction "OSC_OUT_6") (pintype "bidirectional"))
      (node (ref "Q3") (pin "2") (pinfunction "2_2") (pintype "passive"))
    )
    (net (code "66") (name "Net-(IC3A-PC14)") (class "Default")
      (node (ref "C24") (pin "2") (pinfunction "2_2") (pintype "passive"))
      (node (ref "IC3") (pin "3") (pinfunction "PC14_3") (pintype "bidirectional"))
      (node (ref "Q5") (pin "1") (pinfunction "1_1") (pintype "passive"))
    )
    (net (code "67") (name "Net-(IC3A-PC15)") (class "Default")
      (node (ref "C25") (pin "2") (pinfunction "2_2") (pintype "passive"))
      (node (ref "IC3") (pin "4") (pinfunction "PC15_4") (pintype "bidirectional"))
      (node (ref "Q5") (pin "4") (pinfunction "2_4") (pintype "passive"))
    )
    (net (code "68") (name "Net-(IC3A-VCAP1)") (class "Default")
      (node (ref "C8") (pin "2") (pinfunction "2_2") (pintype "passive"))
      (node (ref "IC3") (pin "31") (pinfunction "VCAP1_31") (pintype "power_in"))
    )
    (net (code "69") (name "Net-(IC3A-VCAP2)") (class "Default")
      (node (ref "C9") (pin "2") (pinfunction "2_2") (pintype "passive"))
      (node (ref "IC3") (pin "47") (pinfunction "VCAP2_47") (pintype "power_in"))
    )
    (net (code "70") (name "Net-(IC5-OUT)") (class "Default")
      (node (ref "C26") (pin "2") (pinfunction "2_2") (pintype "passive"))
      (node (ref "IC5") (pin "1") (pinfunction "OUT_1") (pintype "bidirectional"))
    )
    (net (code "71") (name "Net-(IC6-OUT)") (class "Default")
      (node (ref "C27") (pin "2") (pinfunction "2_2") (pintype "passive"))
      (node (ref "IC6") (pin "1") (pinfunction "OUT_1") (pintype "bidirectional"))
    )
    (net (code "72") (name "Net-(IC7-VIN)") (class "Default")
      (node (ref "C22") (pin "1") (pinfunction "1_1") (pintype "passive"))
      (node (ref "IC7") (pin "3") (pinfunction "VIN_3") (pintype "input"))
      (node (ref "Q6") (pin "3") (pinfunction "D_3") (pintype "passive"))
    )
    (net (code "73") (name "Net-(IC8-+OUT_L)") (class "Default")
      (node (ref "IC8") (pin "1") (pinfunction "+OUT_L_1") (pintype "bidirectional"))
      (node (ref "LSP3") (pin "MP") (pinfunction "MP_MP") (pintype "passive"))
    )
    (net (code "74") (name "Net-(IC8-+OUT_R)") (class "Default")
      (node (ref "IC8") (pin "16") (pinfunction "+OUT_R_16") (pintype "bidirectional"))
      (node (ref "OUTL") (pin "MP") (pinfunction "MP_MP") (pintype "passive"))
    )
    (net (code "75") (name "Net-(IC8--OUT_L)") (class "Default")
      (node (ref "IC8") (pin "3") (pinfunction "-OUT_L_3") (pintype "bidirectional"))
      (node (ref "OUTR") (pin "MP") (pinfunction "MP_MP") (pintype "passive"))
    )
    (net (code "76") (name "Net-(IC8--OUT_R)") (class "Default")
      (node (ref "IC8") (pin "14") (pinfunction "-OUT_R_14") (pintype "bidirectional"))
      (node (ref "LSP2") (pin "MP") (pinfunction "MP_MP") (pintype "passive"))
    )
    (net (code "77") (name "Net-(IC8-INL)") (class "Default")
      (node (ref "IC8") (pin "7") (pinfunction "INL_7") (pintype "bidirectional"))
      (node (ref "R11") (pin "2") (pinfunction "2_2") (pintype "passive"))
    )
    (net (code "78") (name "Net-(IC8-INR)") (class "Default")
      (node (ref "IC8") (pin "10") (pinfunction "INR_10") (pintype "bidirectional"))
      (node (ref "R12") (pin "2") (pinfunction "2_2") (pintype "passive"))
    )
    (net (code "79") (name "Net-(IC8-VREF)") (class "Default")
      (node (ref "C28") (pin "2") (pinfunction "2_2") (pintype "passive"))
      (node (ref "IC8") (pin "8") (pinfunction "VREF_8") (pintype "bidirectional"))
    )
    (net (code "80") (name "Net-(IC11-ANT1)") (class "Default")
      (node (ref "A1") (pin "A1") (pinfunction "A1_A1") (pintype "bidirectional"))
      (node (ref "IC11") (pin "LP4") (pinfunction "ANT1_LP4") (pintype "bidirectional"))
    )
    (net (code "81") (name "Net-(IC11-ANT2)") (class "Default")
      (node (ref "A1") (pin "A2") (pinfunction "A2_A2") (pintype "bidirectional"))
      (node (ref "IC11") (pin "LP3") (pinfunction "ANT2_LP3") (pintype "bidirectional"))
    )
    (net (code "82") (name "Net-(IC11-ON)") (class "Default")
      (node (ref "IC11") (pin "LP5") (pinfunction "ON_LP5") (pintype "bidirectional"))
      (node (ref "R4") (pin "2") (pinfunction "2_2") (pintype "passive"))
    )
    (net (code "83") (name "Net-(L5-Pad2)") (class "Default")
      (node (ref "L5") (pin "2") (pinfunction "2_2") (pintype "passive"))
      (node (ref "X3") (pin "DAT1") (pinfunction "DAT1_DAT1") (pintype "bidirectional"))
    )
    (net (code "84") (name "Net-(L6-Pad2)") (class "Default")
      (node (ref "L6") (pin "2") (pinfunction "2_2") (pintype "passive"))
      (node (ref "X3") (pin "DAT0") (pinfunction "DAT0_DAT0") (pintype "bidirectional"))
    )
    (net (code "85") (name "Net-(L7-Pad2)") (class "Default")
      (node (ref "L7") (pin "2") (pinfunction "2_2") (pintype "passive"))
      (node (ref "X3") (pin "CLK") (pinfunction "CLK_CLK") (pintype "bidirectional"))
    )
    (net (code "86") (name "Net-(L8-Pad2)") (class "Default")
      (node (ref "L8") (pin "2") (pinfunction "2_2") (pintype "passive"))
      (node (ref "X3") (pin "CMD") (pinfunction "CMD_CMD") (pintype "bidirectional"))
    )
    (net (code "87") (name "Net-(L9-Pad2)") (class "Default")
      (node (ref "L9") (pin "2") (pinfunction "2_2") (pintype "passive"))
      (node (ref "X3") (pin "CD/DAT3") (pinfunction "CD/DAT3_CD/DAT3") (pintype "bidirectional"))
    )
    (net (code "88") (name "Net-(L10-Pad2)") (class "Default")
      (node (ref "L10") (pin "2") (pinfunction "2_2") (pintype "passive"))
      (node (ref "X3") (pin "DAT2") (pinfunction "DAT2_DAT2") (pintype "bidirectional"))
    )
    (net (code "89") (name "Net-(LED1-PadC)") (class "Default")
      (node (ref "LED1") (pin "C") (pinfunction "C_C") (pintype "passive"))
      (node (ref "R16") (pin "2") (pinfunction "2_2") (pintype "passive"))
    )
    (net (code "90") (name "Net-(Q1-D)") (class "Default")
      (node (ref "Q1") (pin "3") (pinfunction "D_3") (pintype "passive"))
      (node (ref "Q2") (pin "1") (pinfunction "G_1") (pintype "passive"))
      (node (ref "R5") (pin "1") (pinfunction "1_1") (pintype "passive"))
    )
    (net (code "91") (name "Net-(Q1-S)") (class "Default")
      (node (ref "Q1") (pin "2") (pinfunction "S_2") (pintype "passive"))
      (node (ref "R2") (pin "2") (pinfunction "2_2") (pintype "passive"))
    )
    (net (code "92") (name "Net-(Q4-D)") (class "Default")
      (node (ref "Q4") (pin "3") (pinfunction "D_3") (pintype "passive"))
      (node (ref "Q6") (pin "1") (pinfunction "G_1") (pintype "passive"))
      (node (ref "R10") (pin "1") (pinfunction "1_1") (pintype "passive"))
    )
    (net (code "93") (name "Net-(Q4-S)") (class "Default")
      (node (ref "Q4") (pin "2") (pinfunction "S_2") (pintype "passive"))
      (node (ref "R8") (pin "2") (pinfunction "2_2") (pintype "passive"))
    )
    (net (code "94") (name "Net-(Q7-D)") (class "Default")
      (node (ref "Q7") (pin "3") (pinfunction "D_3") (pintype "passive"))
      (node (ref "Q8") (pin "1") (pinfunction "G_1") (pintype "passive"))
      (node (ref "R17") (pin "1") (pinfunction "1_1") (pintype "passive"))
    )
    (net (code "95") (name "Net-(Q7-S)") (class "Default")
      (node (ref "Q7") (pin "2") (pinfunction "S_2") (pintype "passive"))
      (node (ref "R15") (pin "2") (pinfunction "2_2") (pintype "passive"))
    )
    (net (code "96") (name "Net-(SG1-2)") (class "Default")
      (node (ref "R13") (pin "1") (pinfunction "1_1") (pintype "passive"))
      (node (ref "SG1") (pin "-") (pinfunction "2_-") (pintype "passive"))
    )
    (net (code "97") (name "VCC") (class "Default")
      (node (ref "C11") (pin "2") (pinfunction "2_2") (pintype "passive"))
      (node (ref "C2") (pin "2") (pinfunction "2_2") (pintype "passive"))
      (node (ref "C3") (pin "2") (pinfunction "2_2") (pintype "passive"))
      (node (ref "C30") (pin "2") (pinfunction "2_2") (pintype "passive"))
      (node (ref "C31") (pin "2") (pinfunction "2_2") (pintype "passive"))
      (node (ref "C4") (pin "2") (pinfunction "2_2") (pintype "passive"))
      (node (ref "C5") (pin "2") (pinfunction "2_2") (pintype "passive"))
      (node (ref "C6") (pin "2") (pinfunction "2_2") (pintype "passive"))
      (node (ref "C7") (pin "2") (pinfunction "2_2") (pintype "passive"))
      (node (ref "IC1") (pin "2") (pinfunction "VOUT_2") (pintype "power_in"))
      (node (ref "IC10") (pin "VDD") (pinfunction "VDD_VDD") (pintype "power_in"))
      (node (ref "IC11") (pin "LP2") (pinfunction "VCC_LP2") (pintype "power_in"))
      (node (ref "IC3") (pin "1") (pinfunction "VBAT_1") (pintype "power_in"))
      (node (ref "IC3") (pin "13") (pinfunction "VDDA_13") (pintype "power_in"))
      (node (ref "IC3") (pin "19") (pinfunction "VDD_19") (pintype "power_in"))
      (node (ref "IC3") (pin "32") (pinfunction "VDD_32") (pintype "power_in"))
      (node (ref "IC3") (pin "48") (pinfunction "VDD_48") (pintype "power_in"))
      (node (ref "IC3") (pin "64") (pinfunction "VDD_64") (pintype "power_in"))
      (node (ref "OPH1") (pin "2") (pinfunction "2_2") (pintype "passive"))
      (node (ref "Q8") (pin "2") (pinfunction "S_2") (pintype "passive"))
      (node (ref "R17") (pin "2") (pinfunction "2_2") (pintype "passive"))
      (node (ref "SV1") (pin "1") (pinfunction "1_1") (pintype "passive"))
      (node (ref "SV3") (pin "10") (pinfunction "10_10") (pintype "passive"))
    )
    (net (code "98") (name "unconnected-(IC2-CBUS0-Pad23)") (class "Default")
      (node (ref "IC2") (pin "23") (pinfunction "CBUS0_23") (pintype "bidirectional"))
    )
    (net (code "99") (name "unconnected-(IC2-CBUS1-Pad22)") (class "Default")
      (node (ref "IC2") (pin "22") (pinfunction "CBUS1_22") (pintype "bidirectional"))
    )
    (net (code "100") (name "unconnected-(IC2-CBUS2-Pad13)") (class "Default")
      (node (ref "IC2") (pin "13") (pinfunction "CBUS2_13") (pintype "bidirectional"))
    )
    (net (code "101") (name "unconnected-(IC2-CBUS3-Pad14)") (class "Default")
      (node (ref "IC2") (pin "14") (pinfunction "CBUS3_14") (pintype "bidirectional"))
    )
    (net (code "102") (name "unconnected-(IC2-OSCI-Pad27)") (class "Default")
      (node (ref "IC2") (pin "27") (pinfunction "OSCI_27") (pintype "input"))
    )
    (net (code "103") (name "unconnected-(IC2-OSCO-Pad28)") (class "Default")
      (node (ref "IC2") (pin "28") (pinfunction "OSCO_28") (pintype "output"))
    )
    (net (code "104") (name "unconnected-(IC2-~{CTS}-Pad11)") (class "Default")
      (node (ref "IC2") (pin "11") (pinfunction "~{CTS}_11") (pintype "input"))
    )
    (net (code "105") (name "unconnected-(IC2-~{DCD}-Pad10)") (class "Default")
      (node (ref "IC2") (pin "10") (pinfunction "~{DCD}_10") (pintype "input"))
    )
    (net (code "106") (name "unconnected-(IC2-~{DSR}-Pad9)") (class "Default")
      (node (ref "IC2") (pin "9") (pinfunction "~{DSR}_9") (pintype "input"))
    )
    (net (code "107") (name "unconnected-(IC2-~{DTR}-Pad2)") (class "Default")
      (node (ref "IC2") (pin "2") (pinfunction "~{DTR}_2") (pintype "output"))
    )
    (net (code "108") (name "unconnected-(IC2-~{RESET}-Pad19)") (class "Default")
      (node (ref "IC2") (pin "19") (pinfunction "~{RESET}_19") (pintype "input"))
    )
    (net (code "109") (name "unconnected-(IC2-~{RI}-Pad6)") (class "Default")
      (node (ref "IC2") (pin "6") (pinfunction "~{RI}_6") (pintype "input"))
    )
    (net (code "110") (name "unconnected-(IC2-~{RTS}-Pad3)") (class "Default")
      (node (ref "IC2") (pin "3") (pinfunction "~{RTS}_3") (pintype "output"))
    )
    (net (code "111") (name "unconnected-(IC3A-PA4-Pad20)") (class "Default")
      (node (ref "IC3") (pin "20") (pinfunction "PA4_20") (pintype "bidirectional"))
    )
    (net (code "112") (name "unconnected-(IC3A-PA6-Pad22)") (class "Default")
      (node (ref "IC3") (pin "22") (pinfunction "PA6_22") (pintype "bidirectional"))
    )
    (net (code "113") (name "unconnected-(IC3A-PA8-Pad41)") (class "Default")
      (node (ref "IC3") (pin "41") (pinfunction "PA8_41") (pintype "bidirectional"))
    )
    (net (code "114") (name "unconnected-(IC3A-PA9-Pad42)") (class "Default")
      (node (ref "IC3") (pin "42") (pinfunction "PA9_42") (pintype "bidirectional"))
    )
    (net (code "115") (name "unconnected-(IC3A-PA11-Pad44)") (class "Default")
      (node (ref "IC3") (pin "44") (pinfunction "PA11_44") (pintype "bidirectional"))
    )
    (net (code "116") (name "unconnected-(IC3A-PB12-Pad33)") (class "Default")
      (node (ref "IC3") (pin "33") (pinfunction "PB12_33") (pintype "bidirectional"))
    )
    (net (code "117") (name "unconnected-(IC3A-PB14-Pad35)") (class "Default")
      (node (ref "IC3") (pin "35") (pinfunction "PB14_35") (pintype "bidirectional"))
    )
    (net (code "118") (name "unconnected-(IC8-NC-Pad9)") (class "Default")
      (node (ref "IC8") (pin "9") (pinfunction "NC_9") (pintype "bidirectional"))
    )
    (net (code "119") (name "unconnected-(IC11-NC-PadLP7)") (class "Default")
      (node (ref "IC11") (pin "LP7") (pinfunction "NC_LP7") (pintype "bidirectional"))
    )
    (net (code "120") (name "unconnected-(IC11-TEST-PadLP8)") (class "Default")
      (node (ref "IC11") (pin "LP8") (pinfunction "TEST_LP8") (pintype "bidirectional"))
    )
    (net (code "121") (name "unconnected-(R11-Pad1)") (class "Default")
      (node (ref "R11") (pin "1") (pinfunction "1_1") (pintype "passive"))
    )
    (net (code "122") (name "unconnected-(R12-Pad1)") (class "Default")
      (node (ref "R12") (pin "1") (pinfunction "1_1") (pintype "passive"))
    )
    (net (code "123") (name "unconnected-(SV2-Pad5)") (class "Default")
      (node (ref "SV2") (pin "5") (pinfunction "5_5") (pintype "passive"))
    )
    (net (code "124") (name "unconnected-(SV2-Pad6)") (class "Default")
      (node (ref "SV2") (pin "6") (pinfunction "6_6") (pintype "passive"))
    )
    (net (code "125") (name "unconnected-(SV2-Pad7)") (class "Default")
      (node (ref "SV2") (pin "7") (pinfunction "7_7") (pintype "passive"))
    )
    (net (code "126") (name "unconnected-(SV2-Pad8)") (class "Default")
      (node (ref "SV2") (pin "8") (pinfunction "8_8") (pintype "passive"))
    )
    (net (code "127") (name "unconnected-(X1-TERM-Pad1)") (class "Default")
      (node (ref "X1") (pin "1") (pinfunction "TERM_1") (pintype "bidirectional"))
    )
    (net (code "128") (name "unconnected-(X2-Pad4)") (class "Default")
      (node (ref "X2") (pin "4") (pinfunction "4_4") (pintype "passive"))
    )
  )
)
